# Base.net
KiCad netlist of a schematic drawn in EAGLE
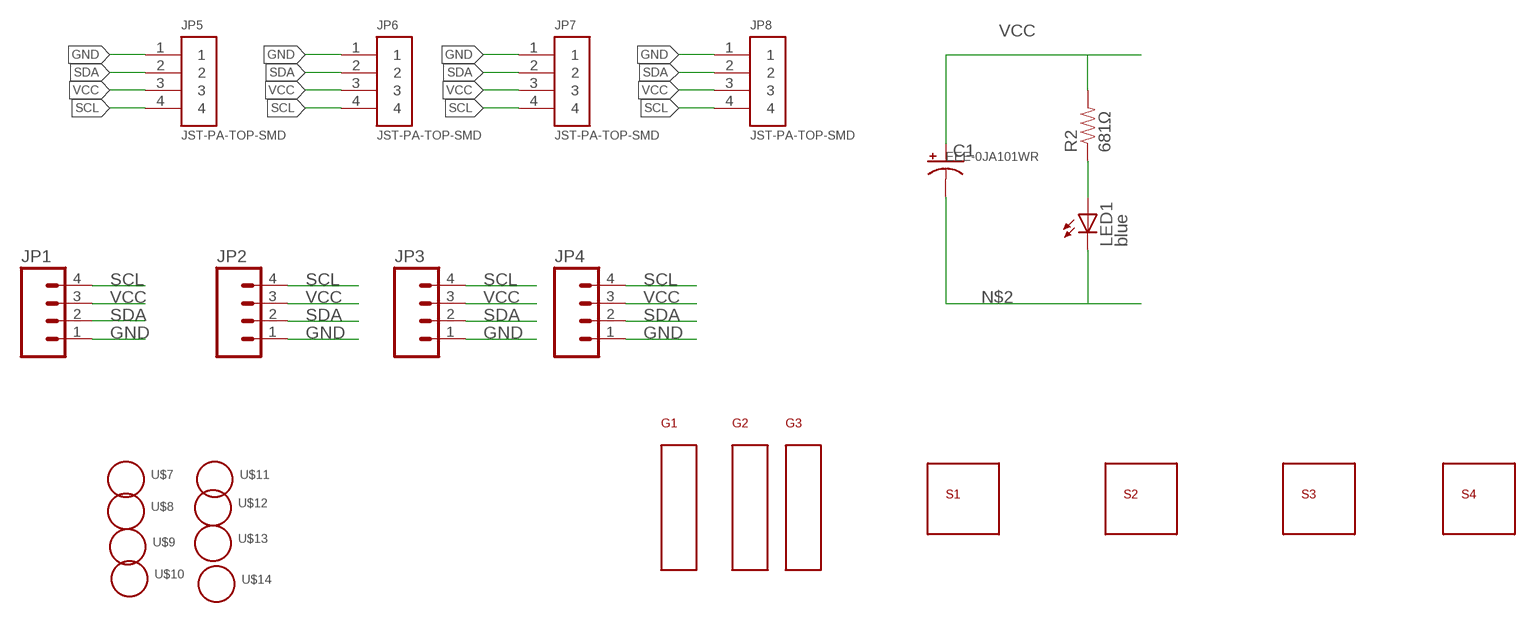
[diagram p0: schematic, sheet 1]

(export (version "E")
  (design (tool "Eeschema 10.0.6"))
  (components
    (comp (ref "C1")
      (value "CAP_POLC")
      (footprint "eagle-import:PANASONIC_C")
      (fields (field (name "PARTNUM") "EEE-0JA101WR"))
      (libsource (lib "eagle-import") (part "CAP_POLC"))
    )
    (comp (ref "G1")
      (value "CARD-GUIDE")
      (footprint "eagle-import:CARD-GUIDE-2_")
      (fields (field (name "PARTNUM") "HCG-201-165"))
      (libsource (lib "eagle-import") (part "CARD-GUIDE"))
    )
    (comp (ref "G2")
      (value "CARD-GUIDE")
      (footprint "eagle-import:CARD-GUIDE-2_")
      (fields (field (name "PARTNUM") "HCG-202-165"))
      (libsource (lib "eagle-import") (part "CARD-GUIDE"))
    )
    (comp (ref "G3")
      (value "CARD-GUIDE")
      (footprint "eagle-import:CARD-GUIDE-2_")
      (fields (field (name "PARTNUM") "HCG-201-165"))
      (libsource (lib "eagle-import") (part "CARD-GUIDE"))
    )
    (comp (ref "JP1")
      (value "M04LOCK")
      (footprint "eagle-import:1X04_LOCK")
      (fields (field (name "PARTNUM") "PPTC041LGBN-RC"))
      (libsource (lib "eagle-import") (part "M04LOCK"))
    )
    (comp (ref "JP2")
      (value "M04LOCK")
      (footprint "eagle-import:1X04_LOCK")
      (fields (field (name "PARTNUM") "PPTC041LGBN-RC"))
      (libsource (lib "eagle-import") (part "M04LOCK"))
    )
    (comp (ref "JP3")
      (value "M04LOCK")
      (footprint "eagle-import:1X04_LOCK")
      (fields (field (name "PARTNUM") "PPTC041LGBN-RC"))
      (libsource (lib "eagle-import") (part "M04LOCK"))
    )
    (comp (ref "JP4")
      (value "M04LOCK")
      (footprint "eagle-import:1X04_LOCK")
      (fields (field (name "PARTNUM") "PPTC041LGBN-RC"))
      (libsource (lib "eagle-import") (part "M04LOCK"))
    )
    (comp (ref "JP5")
      (value "JST-PA-TOP-SMD")
      (footprint "eagle-import:JST-PA-TOP-SMD")
      (fields (field (name "PARTNUM") "BM04B-PASS-1-TFT(LF)(SN)"))
      (libsource (lib "eagle-import") (part "JST-PA-TOP-SMD"))
    )
    (comp (ref "JP6")
      (value "JST-PA-TOP-SMD")
      (footprint "eagle-import:JST-PA-TOP-SMD")
      (fields (field (name "PARTNUM") "BM04B-PASS-1-TFT(LF)(SN)"))
      (libsource (lib "eagle-import") (part "JST-PA-TOP-SMD"))
    )
    (comp (ref "JP7")
      (value "JST-PA-TOP-SMD")
      (footprint "eagle-import:JST-PA-TOP-SMD")
      (fields (field (name "PARTNUM") "BM04B-PASS-1-TFT(LF)(SN)"))
      (libsource (lib "eagle-import") (part "JST-PA-TOP-SMD"))
    )
    (comp (ref "JP8")
      (value "JST-PA-TOP-SMD")
      (footprint "eagle-import:JST-PA-TOP-SMD")
      (fields (field (name "PARTNUM") "BM04B-PASS-1-TFT(LF)(SN)"))
      (libsource (lib "eagle-import") (part "JST-PA-TOP-SMD"))
    )
    (comp (ref "LED1")
      (value "blue")
      (footprint "eagle-import:0805-LED")
      (fields (field (name "PARTNUM") "LTST-C171TBKT"))
      (libsource (lib "eagle-import") (part "LED-0805-BLUE"))
    )
    (comp (ref "R2")
      (value "681Ω")
      (footprint "eagle-import:0603")
      (fields (field (name "PARTNUM") "ERJ-3EKF6810V"))
      (libsource (lib "eagle-import") (part "RESISTOR-681Ω"))
    )
    (comp (ref "S1")
      (value "SPACER")
      (footprint "eagle-import:SPACER")
      (libsource (lib "eagle-import") (part "SPACER"))
    )
    (comp (ref "S2")
      (value "SPACER")
      (footprint "eagle-import:SPACER")
      (libsource (lib "eagle-import") (part "SPACER"))
    )
    (comp (ref "S3")
      (value "SPACER")
      (footprint "eagle-import:SPACER")
      (libsource (lib "eagle-import") (part "SPACER"))
    )
    (comp (ref "S4")
      (value "SPACER")
      (footprint "eagle-import:SPACER")
      (libsource (lib "eagle-import") (part "SPACER"))
    )
    (comp (ref "U$7")
      (value "HOLE#2")
      (footprint "eagle-import:HOLE-#2")
      (fields (field (name "PARTNUM") "EXCLUDE"))
      (libsource (lib "eagle-import") (part "HOLE#2"))
    )
    (comp (ref "U$8")
      (value "HOLE#2")
      (footprint "eagle-import:HOLE-#2")
      (fields (field (name "PARTNUM") "EXCLUDE"))
      (libsource (lib "eagle-import") (part "HOLE#2"))
    )
    (comp (ref "U$9")
      (value "HOLE#2")
      (footprint "eagle-import:HOLE-#2")
      (fields (field (name "PARTNUM") "EXCLUDE"))
      (libsource (lib "eagle-import") (part "HOLE#2"))
    )
    (comp (ref "U$10")
      (value "HOLE#2")
      (footprint "eagle-import:HOLE-#2")
      (fields (field (name "PARTNUM") "EXCLUDE"))
      (libsource (lib "eagle-import") (part "HOLE#2"))
    )
    (comp (ref "U$11")
      (value "HOLE#2")
      (footprint "eagle-import:HOLE-#2")
      (fields (field (name "PARTNUM") "EXCLUDE"))
      (libsource (lib "eagle-import") (part "HOLE#2"))
    )
    (comp (ref "U$12")
      (value "HOLE#2")
      (footprint "eagle-import:HOLE-#2")
      (fields (field (name "PARTNUM") "EXCLUDE"))
      (libsource (lib "eagle-import") (part "HOLE#2"))
    )
    (comp (ref "U$13")
      (value "HOLE#2")
      (footprint "eagle-import:HOLE-#2")
      (fields (field (name "PARTNUM") "EXCLUDE"))
      (libsource (lib "eagle-import") (part "HOLE#2"))
    )
    (comp (ref "U$14")
      (value "HOLE#2")
      (footprint "eagle-import:HOLE-#2")
      (fields (field (name "PARTNUM") "EXCLUDE"))
      (libsource (lib "eagle-import") (part "HOLE#2"))
    )
  )
  (nets
    (net (code "1") (name "/N$2") (class "Default")
      (node (ref "C1") (pin "-") (pinfunction "-_-") (pintype "passive"))
      (node (ref "LED1") (pin "C") (pinfunction "C_C") (pintype "passive"))
    )
    (net (code "2") (name "GND") (class "Default")
      (node (ref "JP1") (pin "1") (pinfunction "1_1") (pintype "passive"))
      (node (ref "JP2") (pin "1") (pinfunction "1_1") (pintype "passive"))
      (node (ref "JP3") (pin "1") (pinfunction "1_1") (pintype "passive"))
      (node (ref "JP4") (pin "1") (pinfunction "1_1") (pintype "passive"))
      (node (ref "JP5") (pin "1") (pinfunction "1_1") (pintype "bidirectional"))
      (node (ref "JP6") (pin "1") (pinfunction "1_1") (pintype "bidirectional"))
      (node (ref "JP7") (pin "1") (pinfunction "1_1") (pintype "bidirectional"))
      (node (ref "JP8") (pin "1") (pinfunction "1_1") (pintype "bidirectional"))
    )
    (net (code "3") (name "Net-(LED1-PadA)") (class "Default")
      (node (ref "LED1") (pin "A") (pinfunction "A_A") (pintype "passive"))
      (node (ref "R2") (pin "1") (pinfunction "1_1") (pintype "passive"))
    )
    (net (code "4") (name "SCL") (class "Default")
      (node (ref "JP1") (pin "4") (pinfunction "4_4") (pintype "passive"))
      (node (ref "JP2") (pin "4") (pinfunction "4_4") (pintype "passive"))
      (node (ref "JP3") (pin "4") (pinfunction "4_4") (pintype "passive"))
      (node (ref "JP4") (pin "4") (pinfunction "4_4") (pintype "passive"))
      (node (ref "JP5") (pin "4") (pinfunction "4_4") (pintype "bidirectional"))
      (node (ref "JP6") (pin "4") (pinfunction "4_4") (pintype "bidirectional"))
      (node (ref "JP7") (pin "4") (pinfunction "4_4") (pintype "bidirectional"))
      (node (ref "JP8") (pin "4") (pinfunction "4_4") (pintype "bidirectional"))
    )
    (net (code "5") (name "SDA") (class "Default")
      (node (ref "JP1") (pin "2") (pinfunction "2_2") (pintype "passive"))
      (node (ref "JP2") (pin "2") (pinfunction "2_2") (pintype "passive"))
      (node (ref "JP3") (pin "2") (pinfunction "2_2") (pintype "passive"))
      (node (ref "JP4") (pin "2") (pinfunction "2_2") (pintype "passive"))
      (node (ref "JP5") (pin "2") (pinfunction "2_2") (pintype "bidirectional"))
      (node (ref "JP6") (pin "2") (pinfunction "2_2") (pintype "bidirectional"))
      (node (ref "JP7") (pin "2") (pinfunction "2_2") (pintype "bidirectional"))
      (node (ref "JP8") (pin "2") (pinfunction "2_2") (pintype "bidirectional"))
    )
    (net (code "6") (name "VCC") (class "Default")
      (node (ref "C1") (pin "+") (pinfunction "+_+") (pintype "passive"))
      (node (ref "JP1") (pin "3") (pinfunction "3_3") (pintype "passive"))
      (node (ref "JP2") (pin "3") (pinfunction "3_3") (pintype "passive"))
      (node (ref "JP3") (pin "3") (pinfunction "3_3") (pintype "passive"))
      (node (ref "JP4") (pin "3") (pinfunction "3_3") (pintype "passive"))
      (node (ref "JP5") (pin "3") (pinfunction "3_3") (pintype "bidirectional"))
      (node (ref "JP6") (pin "3") (pinfunction "3_3") (pintype "bidirectional"))
      (node (ref "JP7") (pin "3") (pinfunction "3_3") (pintype "bidirectional"))
      (node (ref "JP8") (pin "3") (pinfunction "3_3") (pintype "bidirectional"))
      (node (ref "R2") (pin "2") (pinfunction "2_2") (pintype "passive"))
    )
    (net (code "7") (name "unconnected-(U$7-HOLE-PadP$1)") (class "Default")
      (node (ref "U$7") (pin "P$1") (pinfunction "HOLE_P$1") (pintype "bidirectional"))
    )
    (net (code "8") (name "unconnected-(U$8-HOLE-PadP$1)") (class "Default")
      (node (ref "U$8") (pin "P$1") (pinfunction "HOLE_P$1") (pintype "bidirectional"))
    )
    (net (code "9") (name "unconnected-(U$9-HOLE-PadP$1)") (class "Default")
      (node (ref "U$9") (pin "P$1") (pinfunction "HOLE_P$1") (pintype "bidirectional"))
    )
    (net (code "10") (name "unconnected-(U$10-HOLE-PadP$1)") (class "Default")
      (node (ref "U$10") (pin "P$1") (pinfunction "HOLE_P$1") (pintype "bidirectional"))
    )
    (net (code "11") (name "unconnected-(U$11-HOLE-PadP$1)") (class "Default")
      (node (ref "U$11") (pin "P$1") (pinfunction "HOLE_P$1") (pintype "bidirectional"))
    )
    (net (code "12") (name "unconnected-(U$12-HOLE-PadP$1)") (class "Default")
      (node (ref "U$12") (pin "P$1") (pinfunction "HOLE_P$1") (pintype "bidirectional"))
    )
    (net (code "13") (name "unconnected-(U$13-HOLE-PadP$1)") (class "Default")
      (node (ref "U$13") (pin "P$1") (pinfunction "HOLE_P$1") (pintype "bidirectional"))
    )
    (net (code "14") (name "unconnected-(U$14-HOLE-PadP$1)") (class "Default")
      (node (ref "U$14") (pin "P$1") (pinfunction "HOLE_P$1") (pintype "bidirectional"))
    )
  )
)
